# WL-CONNECT.net
KiCad netlist of a schematic drawn in Altium Designer
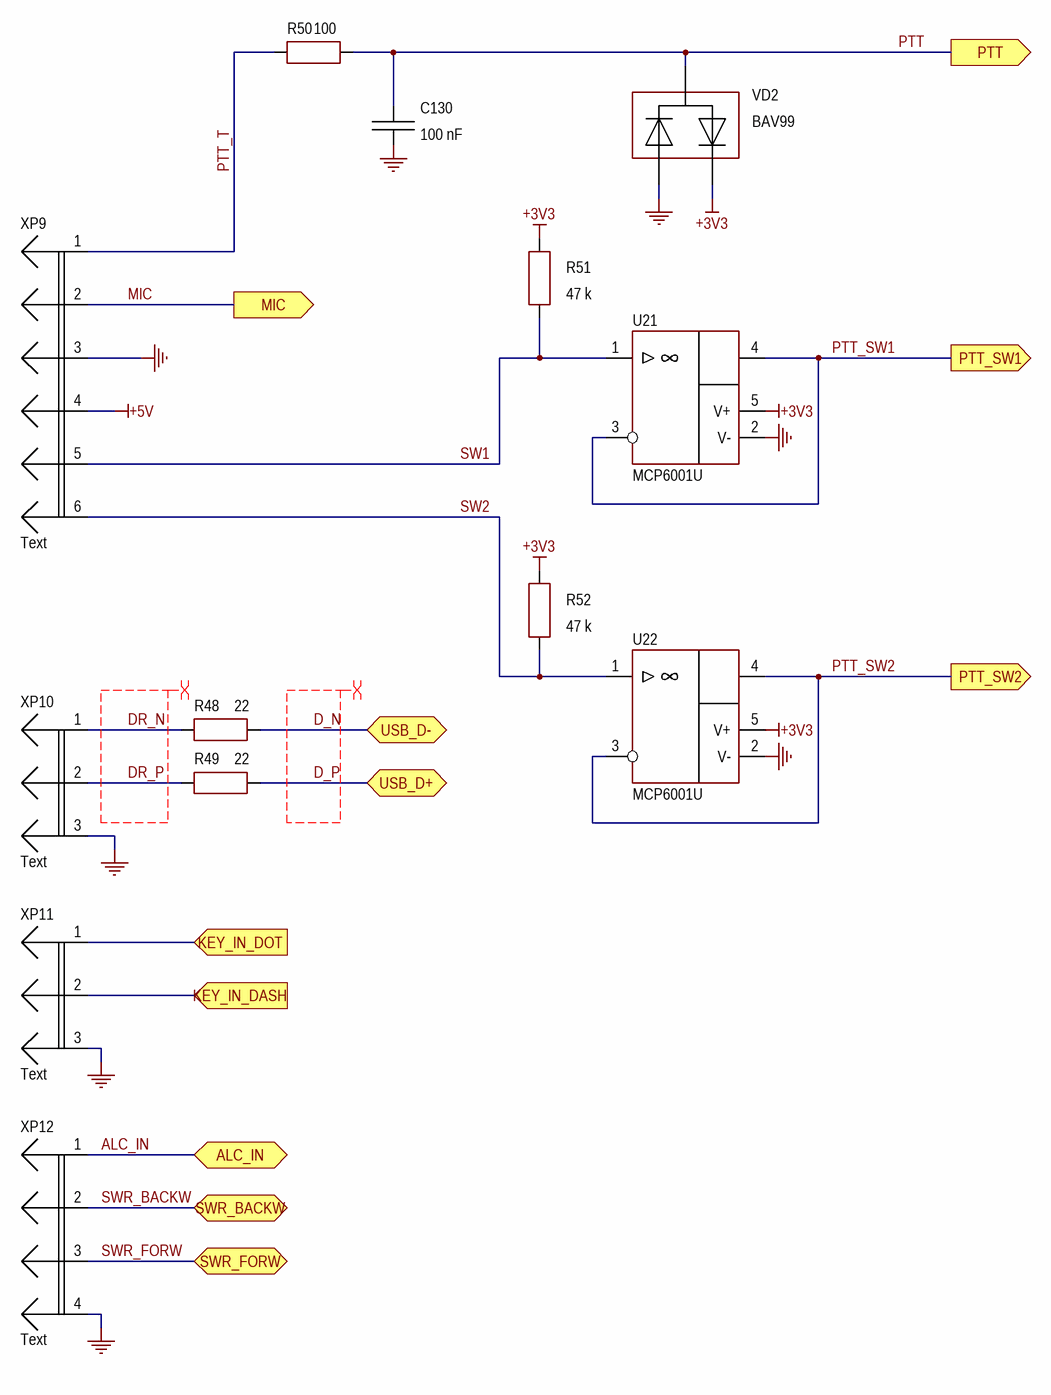
[diagram p0: WL-CONNECT.SchDoc]

(export (version "E")
  (design (tool "Eeschema 10.0.6"))
  (components
    (comp (ref "C130")
      (value "100 nF")
      (footprint "C-0805-0.95")
      (fields
        (field (name "MANUFACTURER") "Yageo")
        (field (name "PART NUMBER") "CC0805KRX7R9BB104")
        (field (name "TOLERANCE") "±10%")
      )
      (libsource (lib "GOST") (part "Capacitor"))
    )
    (comp (ref "R48")
      (value "22")
      (footprint "R-0805")
      (fields
        (field (name "MANUFACTURER") "Yageo")
        (field (name "PART NUMBER") "RC0805JR-0722RL")
        (field (name "POWER") "0,125 W")
      )
      (libsource (lib "") (part "Resistor_1"))
    )
    (comp (ref "R49")
      (value "22")
      (footprint "R-0805")
      (fields
        (field (name "MANUFACTURER") "Yageo")
        (field (name "PART NUMBER") "RC0805JR-0722RL")
        (field (name "POWER") "0,125 W")
      )
      (libsource (lib "") (part "Resistor_1"))
    )
    (comp (ref "R50")
      (value "100")
      (footprint "R-0805")
      (fields
        (field (name "MANUFACTURER") "Yageo")
        (field (name "PART NUMBER") "RC0805JR-07100RL")
        (field (name "POWER") "0,125 W")
      )
      (libsource (lib "") (part "Resistor_1"))
    )
    (comp (ref "R51")
      (value "47 k")
      (footprint "R-0805")
      (fields
        (field (name "MANUFACTURER") "Yageo")
        (field (name "PART NUMBER") "RC0805JR-0747KL")
        (field (name "POWER") "0,125 W")
      )
      (libsource (lib "GOST") (part "Resistor"))
    )
    (comp (ref "R52")
      (value "47 k")
      (footprint "R-0805")
      (fields
        (field (name "MANUFACTURER") "Yageo")
        (field (name "PART NUMBER") "RC0805JR-0747KL")
        (field (name "POWER") "0,125 W")
      )
      (libsource (lib "GOST") (part "Resistor"))
    )
    (comp (ref "U21")
      (value "MCP6001U")
      (footprint "SOT-23-5")
      (description "IC OPAMP GP 1 CIRCUIT SOT-23-5")
      (fields
        (field (name "PART NUMBER") "MCP6001UT-I/OT")
        (field (name "MANUFACTURER") "Microchip Technology")
      )
      (libsource (lib "GOST") (part "MCP6001U"))
    )
    (comp (ref "U22")
      (value "MCP6001U")
      (footprint "SOT-23-5")
      (description "IC OPAMP GP 1 CIRCUIT SOT-23-5")
      (fields
        (field (name "PART NUMBER") "MCP6001UT-I/OT")
        (field (name "MANUFACTURER") "Microchip Technology")
      )
      (libsource (lib "GOST") (part "MCP6001U"))
    )
    (comp (ref "VD2")
      (value "BAV99")
      (footprint "SOT-23")
      (fields (field (name "PART NUMBER") "BAV99,215") (field (name "MANUFACTURER") "Nexperia USA Inc."))
      (libsource (lib "GOST") (part "Schottky Array Common CA"))
    )
    (comp (ref "XP9")
      (value "Text")
      (footprint "61900611121")
      (fields (field (name "PART NUMBER") "61900611121") (field (name "MANUFACTURER") "Würth Elektronik"))
      (libsource (lib "GOST") (part "Con-6-M"))
    )
    (comp (ref "XP10")
      (value "Text")
      (footprint "61900311121")
      (fields (field (name "PART NUMBER") "61900311121") (field (name "MANUFACTURER") "Würth Elektronik"))
      (libsource (lib "GOST") (part "Con-3-M"))
    )
    (comp (ref "XP11")
      (value "Text")
      (footprint "61900311121")
      (fields (field (name "PART NUMBER") "61900311121") (field (name "MANUFACTURER") "Würth Elektronik"))
      (libsource (lib "GOST") (part "Con-3-M"))
    )
    (comp (ref "XP12")
      (value "Text")
      (footprint "61900411121")
      (fields (field (name "PART NUMBER") "61900411121") (field (name "MANUFACTURER") "Würth Elektronik"))
      (libsource (lib "GOST") (part "Con-4-M"))
    )
  )
  (nets
    (net (code "1") (name "+3V3") (class "Default")
      (node (ref "R51") (pin "2") (pinfunction "2_2") (pintype "passive"))
      (node (ref "R52") (pin "2") (pinfunction "2_2") (pintype "passive"))
      (node (ref "U21") (pin "5") (pinfunction "V+_5") (pintype "passive"))
      (node (ref "U22") (pin "5") (pinfunction "V+_5") (pintype "passive"))
      (node (ref "VD2") (pin "2") (pinfunction "2_2") (pintype "passive"))
    )
    (net (code "2") (name "+5V") (class "Default") (node (ref "XP9") (pin "4") (pintype "passive")))
    (net (code "3") (name "/ALC_IN") (class "Default") (node (ref "XP12") (pin "1") (pintype "passive")))
    (net (code "4") (name "/DR_N") (class "Default")
      (node (ref "R48") (pin "1") (pinfunction "1_1") (pintype "passive"))
      (node (ref "XP10") (pin "1") (pintype "passive"))
    )
    (net (code "5") (name "/DR_P") (class "Default")
      (node (ref "R49") (pin "1") (pinfunction "1_1") (pintype "passive"))
      (node (ref "XP10") (pin "2") (pintype "passive"))
    )
    (net (code "6") (name "/D_N") (class "Default")
      (node (ref "R48") (pin "2") (pinfunction "2_2") (pintype "passive"))
    )
    (net (code "7") (name "/D_P") (class "Default")
      (node (ref "R49") (pin "2") (pinfunction "2_2") (pintype "passive"))
    )
    (net (code "8") (name "/KEY_IN_DASH") (class "Default") (node (ref "XP11") (pin "2") (pintype "passive")))
    (net (code "9") (name "/KEY_IN_DOT") (class "Default") (node (ref "XP11") (pin "1") (pintype "passive")))
    (net (code "10") (name "/MIC") (class "Default") (node (ref "XP9") (pin "2") (pintype "passive")))
    (net (code "11") (name "/PTT") (class "Default")
      (node (ref "C130") (pin "2") (pinfunction "2_2") (pintype "passive"))
      (node (ref "R50") (pin "2") (pinfunction "2_2") (pintype "passive"))
      (node (ref "VD2") (pin "3") (pinfunction "3_3") (pintype "passive"))
    )
    (net (code "12") (name "/PTT_SW1") (class "Default")
      (node (ref "U21") (pin "3") (pinfunction "-IN_3") (pintype "passive"))
      (node (ref "U21") (pin "4") (pinfunction "OUT_4") (pintype "passive"))
    )
    (net (code "13") (name "/PTT_SW2") (class "Default")
      (node (ref "U22") (pin "3") (pinfunction "-IN_3") (pintype "passive"))
      (node (ref "U22") (pin "4") (pinfunction "OUT_4") (pintype "passive"))
    )
    (net (code "14") (name "/PTT_T") (class "Default")
      (node (ref "R50") (pin "1") (pinfunction "1_1") (pintype "passive"))
      (node (ref "XP9") (pin "1") (pintype "passive"))
    )
    (net (code "15") (name "/SW1") (class "Default")
      (node (ref "R51") (pin "1") (pinfunction "1_1") (pintype "passive"))
      (node (ref "U21") (pin "1") (pinfunction "+IN_1") (pintype "passive"))
      (node (ref "XP9") (pin "5") (pintype "passive"))
    )
    (net (code "16") (name "/SW2") (class "Default")
      (node (ref "R52") (pin "1") (pinfunction "1_1") (pintype "passive"))
      (node (ref "U22") (pin "1") (pinfunction "+IN_1") (pintype "passive"))
      (node (ref "XP9") (pin "6") (pintype "passive"))
    )
    (net (code "17") (name "/SWR_BACKW") (class "Default") (node (ref "XP12") (pin "2") (pintype "passive")))
    (net (code "18") (name "/SWR_FORW") (class "Default") (node (ref "XP12") (pin "3") (pintype "passive")))
    (net (code "19") (name "GND") (class "Default")
      (node (ref "C130") (pin "1") (pinfunction "1_1") (pintype "passive"))
      (node (ref "U21") (pin "2") (pinfunction "V-_2") (pintype "passive"))
      (node (ref "U22") (pin "2") (pinfunction "V-_2") (pintype "passive"))
      (node (ref "VD2") (pin "1") (pinfunction "1_1") (pintype "passive"))
      (node (ref "XP10") (pin "3") (pintype "passive"))
      (node (ref "XP11") (pin "3") (pintype "passive"))
      (node (ref "XP12") (pin "4") (pintype "passive"))
      (node (ref "XP9") (pin "3") (pintype "passive"))
    )
  )
)
